# Sheet1.net
KiCad netlist of a schematic drawn in Altium Designer
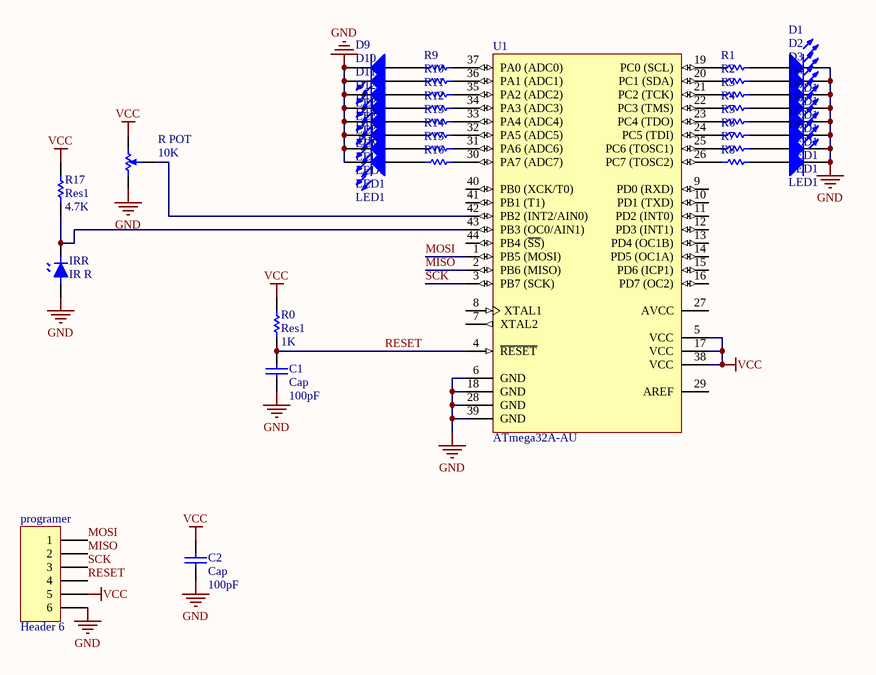
[diagram p0: Sheet1.SchDoc]

(export (version "E")
  (design (tool "Eeschema 10.0.6"))
  (components
    (comp (ref "C1")
      (value "Cap")
      (footprint "PIN2")
      (description "Capacitor")
      (fields (field (name "ALTIUM_VALUE") "100pF") (field (name "PUBLISHER") "Altium Limited"))
      (libsource (lib "Miscellaneous Devices") (part "Cap"))
    )
    (comp (ref "C2")
      (value "Cap")
      (footprint "PIN2")
      (description "Capacitor")
      (fields (field (name "ALTIUM_VALUE") "100pF") (field (name "PUBLISHER") "Altium Limited"))
      (libsource (lib "Miscellaneous Devices") (part "Cap"))
    )
    (comp (ref "D1")
      (value "LED1")
      (footprint "LED-1")
      (description "Typical RED, GREEN, YELLOW, AMBER GaAs LED")
      (fields (field (name "PUBLISHER") "Altium Limited"))
      (libsource (lib "Miscellaneous Devices") (part "LED2"))
    )
    (comp (ref "D2")
      (value "LED1")
      (footprint "LED-1")
      (description "Typical RED, GREEN, YELLOW, AMBER GaAs LED")
      (fields (field (name "PUBLISHER") "Altium Limited"))
      (libsource (lib "Miscellaneous Devices") (part "LED2"))
    )
    (comp (ref "D3")
      (value "LED1")
      (footprint "LED-1")
      (description "Typical RED, GREEN, YELLOW, AMBER GaAs LED")
      (fields (field (name "PUBLISHER") "Altium Limited"))
      (libsource (lib "Miscellaneous Devices") (part "LED2"))
    )
    (comp (ref "D4")
      (value "LED1")
      (footprint "LED-1")
      (description "Typical RED, GREEN, YELLOW, AMBER GaAs LED")
      (fields (field (name "PUBLISHER") "Altium Limited"))
      (libsource (lib "Miscellaneous Devices") (part "LED2"))
    )
    (comp (ref "D5")
      (value "LED1")
      (footprint "LED-1")
      (description "Typical RED, GREEN, YELLOW, AMBER GaAs LED")
      (fields (field (name "PUBLISHER") "Altium Limited"))
      (libsource (lib "Miscellaneous Devices") (part "LED2"))
    )
    (comp (ref "D6")
      (value "LED1")
      (footprint "LED-1")
      (description "Typical RED, GREEN, YELLOW, AMBER GaAs LED")
      (fields (field (name "PUBLISHER") "Altium Limited"))
      (libsource (lib "Miscellaneous Devices") (part "LED2"))
    )
    (comp (ref "D7")
      (value "LED1")
      (footprint "LED-1")
      (description "Typical RED, GREEN, YELLOW, AMBER GaAs LED")
      (fields (field (name "PUBLISHER") "Altium Limited"))
      (libsource (lib "Miscellaneous Devices") (part "LED2"))
    )
    (comp (ref "D8")
      (value "LED1")
      (footprint "LED-1")
      (description "Typical RED, GREEN, YELLOW, AMBER GaAs LED")
      (fields (field (name "PUBLISHER") "Altium Limited"))
      (libsource (lib "Miscellaneous Devices") (part "LED2"))
    )
    (comp (ref "D9")
      (value "LED1")
      (footprint "LED-1")
      (description "Typical RED, GREEN, YELLOW, AMBER GaAs LED")
      (fields (field (name "PUBLISHER") "Altium Limited"))
      (libsource (lib "Miscellaneous Devices") (part "LED2"))
    )
    (comp (ref "D10")
      (value "LED1")
      (footprint "LED-1")
      (description "Typical RED, GREEN, YELLOW, AMBER GaAs LED")
      (fields (field (name "PUBLISHER") "Altium Limited"))
      (libsource (lib "Miscellaneous Devices") (part "LED2"))
    )
    (comp (ref "D11")
      (value "LED1")
      (footprint "LED-1")
      (description "Typical RED, GREEN, YELLOW, AMBER GaAs LED")
      (fields (field (name "PUBLISHER") "Altium Limited"))
      (libsource (lib "Miscellaneous Devices") (part "LED2"))
    )
    (comp (ref "D12")
      (value "LED1")
      (footprint "LED-1")
      (description "Typical RED, GREEN, YELLOW, AMBER GaAs LED")
      (fields (field (name "PUBLISHER") "Altium Limited"))
      (libsource (lib "Miscellaneous Devices") (part "LED2"))
    )
    (comp (ref "D13")
      (value "LED1")
      (footprint "LED-1")
      (description "Typical RED, GREEN, YELLOW, AMBER GaAs LED")
      (fields (field (name "PUBLISHER") "Altium Limited"))
      (libsource (lib "Miscellaneous Devices") (part "LED2"))
    )
    (comp (ref "D14")
      (value "LED1")
      (footprint "LED-1")
      (description "Typical RED, GREEN, YELLOW, AMBER GaAs LED")
      (fields (field (name "PUBLISHER") "Altium Limited"))
      (libsource (lib "Miscellaneous Devices") (part "LED2"))
    )
    (comp (ref "D15")
      (value "LED1")
      (footprint "LED-1")
      (description "Typical RED, GREEN, YELLOW, AMBER GaAs LED")
      (fields (field (name "PUBLISHER") "Altium Limited"))
      (libsource (lib "Miscellaneous Devices") (part "LED2"))
    )
    (comp (ref "D16")
      (value "LED1")
      (footprint "LED-1")
      (description "Typical RED, GREEN, YELLOW, AMBER GaAs LED")
      (fields (field (name "PUBLISHER") "Altium Limited"))
      (libsource (lib "Miscellaneous Devices") (part "LED2"))
    )
    (comp (ref "IRR")
      (value "IR R")
      (footprint "LED-3MM")
      (description "IR Receiver")
      (libsource (lib "IOElectro") (part "IRR"))
    )
    (comp (ref "programer")
      (value "Header 6")
      (footprint "HDR1X6")
      (description "Header, 6-Pin")
      (fields (field (name "PUBLISHER") "Altium Limited"))
      (libsource (lib "Miscellaneous Connectors") (part "Header 6"))
    )
    (comp (ref "R POT")
      (value "10K")
      (footprint "POT4MM-2")
      (description "Square Trimming Potentiometer")
      (fields (field (name "PUBLISHER") "Altium Limited"))
      (libsource (lib "Miscellaneous Devices") (part "RPot SM"))
    )
    (comp (ref "R0")
      (value "Res1")
      (footprint "AXIAL-0.3")
      (description "Resistor")
      (fields (field (name "ALTIUM_VALUE") "1K") (field (name "PUBLISHER") "Altium Limited"))
      (libsource (lib "Miscellaneous Devices") (part "Res1"))
    )
    (comp (ref "R1")
      (value "Res1")
      (footprint "C1206")
      (description "Resistor")
      (fields (field (name "PUBLISHER") "Altium Limited"))
      (libsource (lib "Miscellaneous Devices") (part "Res1"))
    )
    (comp (ref "R2")
      (value "Res1")
      (footprint "C1206")
      (description "Resistor")
      (fields (field (name "PUBLISHER") "Altium Limited"))
      (libsource (lib "Miscellaneous Devices") (part "Res1"))
    )
    (comp (ref "R3")
      (value "Res1")
      (footprint "C1206")
      (description "Resistor")
      (fields (field (name "PUBLISHER") "Altium Limited"))
      (libsource (lib "Miscellaneous Devices") (part "Res1"))
    )
    (comp (ref "R4")
      (value "Res1")
      (footprint "C1206")
      (description "Resistor")
      (fields (field (name "PUBLISHER") "Altium Limited"))
      (libsource (lib "Miscellaneous Devices") (part "Res1"))
    )
    (comp (ref "R5")
      (value "Res1")
      (footprint "C1206")
      (description "Resistor")
      (fields (field (name "PUBLISHER") "Altium Limited"))
      (libsource (lib "Miscellaneous Devices") (part "Res1"))
    )
    (comp (ref "R6")
      (value "Res1")
      (footprint "C1206")
      (description "Resistor")
      (fields (field (name "PUBLISHER") "Altium Limited"))
      (libsource (lib "Miscellaneous Devices") (part "Res1"))
    )
    (comp (ref "R7")
      (value "Res1")
      (footprint "C1206")
      (description "Resistor")
      (fields (field (name "PUBLISHER") "Altium Limited"))
      (libsource (lib "Miscellaneous Devices") (part "Res1"))
    )
    (comp (ref "R8")
      (value "Res1")
      (footprint "C1206")
      (description "Resistor")
      (fields (field (name "PUBLISHER") "Altium Limited"))
      (libsource (lib "Miscellaneous Devices") (part "Res1"))
    )
    (comp (ref "R9")
      (value "Res1")
      (footprint "C1206")
      (description "Resistor")
      (fields (field (name "PUBLISHER") "Altium Limited"))
      (libsource (lib "Miscellaneous Devices") (part "Res1"))
    )
    (comp (ref "R10")
      (value "Res1")
      (footprint "C1206")
      (description "Resistor")
      (fields (field (name "PUBLISHER") "Altium Limited"))
      (libsource (lib "Miscellaneous Devices") (part "Res1"))
    )
    (comp (ref "R11")
      (value "Res1")
      (footprint "C1206")
      (description "Resistor")
      (fields (field (name "PUBLISHER") "Altium Limited"))
      (libsource (lib "Miscellaneous Devices") (part "Res1"))
    )
    (comp (ref "R12")
      (value "Res1")
      (footprint "C1206")
      (description "Resistor")
      (fields (field (name "PUBLISHER") "Altium Limited"))
      (libsource (lib "Miscellaneous Devices") (part "Res1"))
    )
    (comp (ref "R13")
      (value "Res1")
      (footprint "C1206")
      (description "Resistor")
      (fields (field (name "PUBLISHER") "Altium Limited"))
      (libsource (lib "Miscellaneous Devices") (part "Res1"))
    )
    (comp (ref "R14")
      (value "Res1")
      (footprint "C1206")
      (description "Resistor")
      (fields (field (name "PUBLISHER") "Altium Limited"))
      (libsource (lib "Miscellaneous Devices") (part "Res1"))
    )
    (comp (ref "R15")
      (value "Res1")
      (footprint "C1206")
      (description "Resistor")
      (fields (field (name "PUBLISHER") "Altium Limited"))
      (libsource (lib "Miscellaneous Devices") (part "Res1"))
    )
    (comp (ref "R16")
      (value "Res1")
      (footprint "C1206")
      (description "Resistor")
      (fields (field (name "PUBLISHER") "Altium Limited"))
      (libsource (lib "Miscellaneous Devices") (part "Res1"))
    )
    (comp (ref "R17")
      (value "Res1")
      (footprint "AXIAL-0.3")
      (description "Resistor")
      (fields (field (name "ALTIUM_VALUE") "4.7K") (field (name "PUBLISHER") "Altium Limited"))
      (libsource (lib "Miscellaneous Devices") (part "Res1"))
    )
    (comp (ref "U1")
      (value "ATmega32A-AU")
      (footprint "44A_N")
      (fields (field (name "PUBLISHER") "Altium Limited"))
      (libsource (lib "Atmel Microcontroller 8-Bit megaAVR") (part "ATmega32A-AU"))
    )
  )
  (nets
    (net (code "1") (name "/MISO") (class "Default")
      (node (ref "U1") (pin "2") (pinfunction "PB6_(MISO)_2") (pintype "bidirectional"))
      (node (ref "programer") (pin "2") (pinfunction "2_2") (pintype "passive"))
    )
    (net (code "2") (name "/MOSI") (class "Default")
      (node (ref "U1") (pin "1") (pinfunction "PB5_(MOSI)_1") (pintype "bidirectional"))
      (node (ref "programer") (pin "1") (pinfunction "1_1") (pintype "passive"))
    )
    (net (code "3") (name "/RESET") (class "Default")
      (node (ref "C1") (pin "2") (pinfunction "2_2") (pintype "passive"))
      (node (ref "R0") (pin "1") (pinfunction "1_1") (pintype "passive"))
      (node (ref "U1") (pin "4") (pinfunction "~{RESET}_4") (pintype "input"))
      (node (ref "programer") (pin "4") (pinfunction "4_4") (pintype "passive"))
    )
    (net (code "4") (name "/SCK") (class "Default")
      (node (ref "U1") (pin "3") (pinfunction "PB7_(SCK)_3") (pintype "bidirectional"))
      (node (ref "programer") (pin "3") (pinfunction "3_3") (pintype "passive"))
    )
    (net (code "5") (name "GND") (class "Default")
      (node (ref "C1") (pin "1") (pinfunction "1_1") (pintype "passive"))
      (node (ref "C2") (pin "1") (pinfunction "1_1") (pintype "passive"))
      (node (ref "D1") (pin "2") (pinfunction "K_2") (pintype "passive"))
      (node (ref "D10") (pin "2") (pinfunction "K_2") (pintype "passive"))
      (node (ref "D11") (pin "2") (pinfunction "K_2") (pintype "passive"))
      (node (ref "D12") (pin "2") (pinfunction "K_2") (pintype "passive"))
      (node (ref "D13") (pin "2") (pinfunction "K_2") (pintype "passive"))
      (node (ref "D14") (pin "2") (pinfunction "K_2") (pintype "passive"))
      (node (ref "D15") (pin "2") (pinfunction "K_2") (pintype "passive"))
      (node (ref "D16") (pin "2") (pinfunction "K_2") (pintype "passive"))
      (node (ref "D2") (pin "2") (pinfunction "K_2") (pintype "passive"))
      (node (ref "D3") (pin "2") (pinfunction "K_2") (pintype "passive"))
      (node (ref "D4") (pin "2") (pinfunction "K_2") (pintype "passive"))
      (node (ref "D5") (pin "2") (pinfunction "K_2") (pintype "passive"))
      (node (ref "D6") (pin "2") (pinfunction "K_2") (pintype "passive"))
      (node (ref "D7") (pin "2") (pinfunction "K_2") (pintype "passive"))
      (node (ref "D8") (pin "2") (pinfunction "K_2") (pintype "passive"))
      (node (ref "D9") (pin "2") (pinfunction "K_2") (pintype "passive"))
      (node (ref "IRR") (pin "A") (pinfunction "A_A") (pintype "passive"))
      (node (ref "R POT") (pin "CCW") (pinfunction "-_CCW") (pintype "passive"))
      (node (ref "U1") (pin "18") (pinfunction "GND_18") (pintype "power_in"))
      (node (ref "U1") (pin "28") (pinfunction "GND_28") (pintype "power_in"))
      (node (ref "U1") (pin "39") (pinfunction "GND_39") (pintype "power_in"))
      (node (ref "U1") (pin "6") (pinfunction "GND_6") (pintype "power_in"))
      (node (ref "programer") (pin "6") (pinfunction "6_6") (pintype "passive"))
    )
    (net (code "6") (name "Net-(D1-A)") (class "Default")
      (node (ref "D1") (pin "1") (pinfunction "A_1") (pintype "passive"))
      (node (ref "R1") (pin "2") (pinfunction "2_2") (pintype "passive"))
    )
    (net (code "7") (name "Net-(D2-A)") (class "Default")
      (node (ref "D2") (pin "1") (pinfunction "A_1") (pintype "passive"))
      (node (ref "R2") (pin "2") (pinfunction "2_2") (pintype "passive"))
    )
    (net (code "8") (name "Net-(D3-A)") (class "Default")
      (node (ref "D3") (pin "1") (pinfunction "A_1") (pintype "passive"))
      (node (ref "R3") (pin "2") (pinfunction "2_2") (pintype "passive"))
    )
    (net (code "9") (name "Net-(D4-A)") (class "Default")
      (node (ref "D4") (pin "1") (pinfunction "A_1") (pintype "passive"))
      (node (ref "R4") (pin "2") (pinfunction "2_2") (pintype "passive"))
    )
    (net (code "10") (name "Net-(D5-A)") (class "Default")
      (node (ref "D5") (pin "1") (pinfunction "A_1") (pintype "passive"))
      (node (ref "R5") (pin "2") (pinfunction "2_2") (pintype "passive"))
    )
    (net (code "11") (name "Net-(D6-A)") (class "Default")
      (node (ref "D6") (pin "1") (pinfunction "A_1") (pintype "passive"))
      (node (ref "R6") (pin "2") (pinfunction "2_2") (pintype "passive"))
    )
    (net (code "12") (name "Net-(D7-A)") (class "Default")
      (node (ref "D7") (pin "1") (pinfunction "A_1") (pintype "passive"))
      (node (ref "R7") (pin "2") (pinfunction "2_2") (pintype "passive"))
    )
    (net (code "13") (name "Net-(D8-A)") (class "Default")
      (node (ref "D8") (pin "1") (pinfunction "A_1") (pintype "passive"))
      (node (ref "R8") (pin "2") (pinfunction "2_2") (pintype "passive"))
    )
    (net (code "14") (name "Net-(D9-A)") (class "Default")
      (node (ref "D9") (pin "1") (pinfunction "A_1") (pintype "passive"))
      (node (ref "R9") (pin "2") (pinfunction "2_2") (pintype "passive"))
    )
    (net (code "15") (name "Net-(D10-A)") (class "Default")
      (node (ref "D10") (pin "1") (pinfunction "A_1") (pintype "passive"))
      (node (ref "R10") (pin "2") (pinfunction "2_2") (pintype "passive"))
    )
    (net (code "16") (name "Net-(D11-A)") (class "Default")
      (node (ref "D11") (pin "1") (pinfunction "A_1") (pintype "passive"))
      (node (ref "R11") (pin "2") (pinfunction "2_2") (pintype "passive"))
    )
    (net (code "17") (name "Net-(D12-A)") (class "Default")
      (node (ref "D12") (pin "1") (pinfunction "A_1") (pintype "passive"))
      (node (ref "R12") (pin "2") (pinfunction "2_2") (pintype "passive"))
    )
    (net (code "18") (name "Net-(D13-A)") (class "Default")
      (node (ref "D13") (pin "1") (pinfunction "A_1") (pintype "passive"))
      (node (ref "R13") (pin "2") (pinfunction "2_2") (pintype "passive"))
    )
    (net (code "19") (name "Net-(D14-A)") (class "Default")
      (node (ref "D14") (pin "1") (pinfunction "A_1") (pintype "passive"))
      (node (ref "R14") (pin "2") (pinfunction "2_2") (pintype "passive"))
    )
    (net (code "20") (name "Net-(D15-A)") (class "Default")
      (node (ref "D15") (pin "1") (pinfunction "A_1") (pintype "passive"))
      (node (ref "R15") (pin "2") (pinfunction "2_2") (pintype "passive"))
    )
    (net (code "21") (name "Net-(D16-A)") (class "Default")
      (node (ref "D16") (pin "1") (pinfunction "A_1") (pintype "passive"))
      (node (ref "R16") (pin "2") (pinfunction "2_2") (pintype "passive"))
    )
    (net (code "22") (name "Net-(U1-PA0_(ADC0))") (class "Default")
      (node (ref "R9") (pin "1") (pinfunction "1_1") (pintype "passive"))
      (node (ref "U1") (pin "37") (pinfunction "PA0_(ADC0)_37") (pintype "bidirectional"))
    )
    (net (code "23") (name "Net-(U1-PA1_(ADC1))") (class "Default")
      (node (ref "R10") (pin "1") (pinfunction "1_1") (pintype "passive"))
      (node (ref "U1") (pin "36") (pinfunction "PA1_(ADC1)_36") (pintype "bidirectional"))
    )
    (net (code "24") (name "Net-(U1-PA2_(ADC2))") (class "Default")
      (node (ref "R11") (pin "1") (pinfunction "1_1") (pintype "passive"))
      (node (ref "U1") (pin "35") (pinfunction "PA2_(ADC2)_35") (pintype "bidirectional"))
    )
    (net (code "25") (name "Net-(U1-PA3_(ADC3))") (class "Default")
      (node (ref "R12") (pin "1") (pinfunction "1_1") (pintype "passive"))
      (node (ref "U1") (pin "34") (pinfunction "PA3_(ADC3)_34") (pintype "bidirectional"))
    )
    (net (code "26") (name "Net-(U1-PA4_(ADC4))") (class "Default")
      (node (ref "R13") (pin "1") (pinfunction "1_1") (pintype "passive"))
      (node (ref "U1") (pin "33") (pinfunction "PA4_(ADC4)_33") (pintype "bidirectional"))
    )
    (net (code "27") (name "Net-(U1-PA5_(ADC5))") (class "Default")
      (node (ref "R14") (pin "1") (pinfunction "1_1") (pintype "passive"))
      (node (ref "U1") (pin "32") (pinfunction "PA5_(ADC5)_32") (pintype "bidirectional"))
    )
    (net (code "28") (name "Net-(U1-PA6_(ADC6))") (class "Default")
      (node (ref "R15") (pin "1") (pinfunction "1_1") (pintype "passive"))
      (node (ref "U1") (pin "31") (pinfunction "PA6_(ADC6)_31") (pintype "bidirectional"))
    )
    (net (code "29") (name "Net-(U1-PA7_(ADC7))") (class "Default")
      (node (ref "R16") (pin "1") (pinfunction "1_1") (pintype "passive"))
      (node (ref "U1") (pin "30") (pinfunction "PA7_(ADC7)_30") (pintype "bidirectional"))
    )
    (net (code "30") (name "Net-(U1-PB2_(INT2{slash}AIN0))") (class "Default")
      (node (ref "R POT") (pin "W") (pinfunction "W_W") (pintype "passive"))
      (node (ref "U1") (pin "42") (pinfunction "PB2_(INT2/AIN0)_42") (pintype "bidirectional"))
    )
    (net (code "31") (name "Net-(U1-PB3_(OC0{slash}AIN1))") (class "Default")
      (node (ref "IRR") (pin "K") (pinfunction "K_K") (pintype "passive"))
      (node (ref "R17") (pin "1") (pinfunction "1_1") (pintype "passive"))
      (node (ref "U1") (pin "43") (pinfunction "PB3_(OC0/AIN1)_43") (pintype "bidirectional"))
    )
    (net (code "32") (name "Net-(U1-PC0_(SCL))") (class "Default")
      (node (ref "R1") (pin "1") (pinfunction "1_1") (pintype "passive"))
      (node (ref "U1") (pin "19") (pinfunction "PC0_(SCL)_19") (pintype "bidirectional"))
    )
    (net (code "33") (name "Net-(U1-PC1_(SDA))") (class "Default")
      (node (ref "R2") (pin "1") (pinfunction "1_1") (pintype "passive"))
      (node (ref "U1") (pin "20") (pinfunction "PC1_(SDA)_20") (pintype "bidirectional"))
    )
    (net (code "34") (name "Net-(U1-PC2_(TCK))") (class "Default")
      (node (ref "R3") (pin "1") (pinfunction "1_1") (pintype "passive"))
      (node (ref "U1") (pin "21") (pinfunction "PC2_(TCK)_21") (pintype "bidirectional"))
    )
    (net (code "35") (name "Net-(U1-PC3_(TMS))") (class "Default")
      (node (ref "R4") (pin "1") (pinfunction "1_1") (pintype "passive"))
      (node (ref "U1") (pin "22") (pinfunction "PC3_(TMS)_22") (pintype "bidirectional"))
    )
    (net (code "36") (name "Net-(U1-PC4_(TDO))") (class "Default")
      (node (ref "R5") (pin "1") (pinfunction "1_1") (pintype "passive"))
      (node (ref "U1") (pin "23") (pinfunction "PC4_(TDO)_23") (pintype "bidirectional"))
    )
    (net (code "37") (name "Net-(U1-PC5_(TDI))") (class "Default")
      (node (ref "R6") (pin "1") (pinfunction "1_1") (pintype "passive"))
      (node (ref "U1") (pin "24") (pinfunction "PC5_(TDI)_24") (pintype "bidirectional"))
    )
    (net (code "38") (name "Net-(U1-PC6_(TOSC1))") (class "Default")
      (node (ref "R7") (pin "1") (pinfunction "1_1") (pintype "passive"))
      (node (ref "U1") (pin "25") (pinfunction "PC6_(TOSC1)_25") (pintype "bidirectional"))
    )
    (net (code "39") (name "Net-(U1-PC7_(TOSC2))") (class "Default")
      (node (ref "R8") (pin "1") (pinfunction "1_1") (pintype "passive"))
      (node (ref "U1") (pin "26") (pinfunction "PC7_(TOSC2)_26") (pintype "bidirectional"))
    )
    (net (code "40") (name "VCC") (class "Default")
      (node (ref "C2") (pin "2") (pinfunction "2_2") (pintype "passive"))
      (node (ref "R POT") (pin "CW") (pinfunction "+_CW") (pintype "passive"))
      (node (ref "R0") (pin "2") (pinfunction "2_2") (pintype "passive"))
      (node (ref "R17") (pin "2") (pinfunction "2_2") (pintype "passive"))
      (node (ref "U1") (pin "17") (pinfunction "VCC_17") (pintype "power_in"))
      (node (ref "U1") (pin "38") (pinfunction "VCC_38") (pintype "power_in"))
      (node (ref "U1") (pin "5") (pinfunction "VCC_5") (pintype "power_in"))
      (node (ref "programer") (pin "5") (pinfunction "5_5") (pintype "passive"))
    )
    (net (code "41") (name "unconnected-(U1-AREF-Pad29)") (class "Default")
      (node (ref "U1") (pin "29") (pinfunction "AREF_29") (pintype "power_in"))
    )
    (net (code "42") (name "unconnected-(U1-AVCC-Pad27)") (class "Default")
      (node (ref "U1") (pin "27") (pinfunction "AVCC_27") (pintype "power_in"))
    )
    (net (code "43") (name "unconnected-(U1-PB0_(XCK{slash}T0)-Pad40)") (class "Default")
      (node (ref "U1") (pin "40") (pinfunction "PB0_(XCK/T0)_40") (pintype "bidirectional"))
    )
    (net (code "44") (name "unconnected-(U1-PB1_(T1)-Pad41)") (class "Default")
      (node (ref "U1") (pin "41") (pinfunction "PB1_(T1)_41") (pintype "bidirectional"))
    )
    (net (code "45") (name "unconnected-(U1-PB4_(~{SS})-Pad44)") (class "Default")
      (node (ref "U1") (pin "44") (pinfunction "PB4_(~{SS})_44") (pintype "bidirectional"))
    )
    (net (code "46") (name "unconnected-(U1-PD0_(RXD)-Pad9)") (class "Default")
      (node (ref "U1") (pin "9") (pinfunction "PD0_(RXD)_9") (pintype "bidirectional"))
    )
    (net (code "47") (name "unconnected-(U1-PD1_(TXD)-Pad10)") (class "Default")
      (node (ref "U1") (pin "10") (pinfunction "PD1_(TXD)_10") (pintype "bidirectional"))
    )
    (net (code "48") (name "unconnected-(U1-PD2_(INT0)-Pad11)") (class "Default")
      (node (ref "U1") (pin "11") (pinfunction "PD2_(INT0)_11") (pintype "bidirectional"))
    )
    (net (code "49") (name "unconnected-(U1-PD3_(INT1)-Pad12)") (class "Default")
      (node (ref "U1") (pin "12") (pinfunction "PD3_(INT1)_12") (pintype "bidirectional"))
    )
    (net (code "50") (name "unconnected-(U1-PD4_(OC1B)-Pad13)") (class "Default")
      (node (ref "U1") (pin "13") (pinfunction "PD4_(OC1B)_13") (pintype "bidirectional"))
    )
    (net (code "51") (name "unconnected-(U1-PD5_(OC1A)-Pad14)") (class "Default")
      (node (ref "U1") (pin "14") (pinfunction "PD5_(OC1A)_14") (pintype "bidirectional"))
    )
    (net (code "52") (name "unconnected-(U1-PD6_(ICP1)-Pad15)") (class "Default")
      (node (ref "U1") (pin "15") (pinfunction "PD6_(ICP1)_15") (pintype "bidirectional"))
    )
    (net (code "53") (name "unconnected-(U1-PD7_(OC2)-Pad16)") (class "Default")
      (node (ref "U1") (pin "16") (pinfunction "PD7_(OC2)_16") (pintype "bidirectional"))
    )
    (net (code "54") (name "unconnected-(U1-XTAL1-Pad8)") (class "Default")
      (node (ref "U1") (pin "8") (pinfunction "XTAL1_8") (pintype "input"))
    )
    (net (code "55") (name "unconnected-(U1-XTAL2-Pad7)") (class "Default")
      (node (ref "U1") (pin "7") (pinfunction "XTAL2_7") (pintype "output"))
    )
  )
)
